# GPIOSheet.net
KiCad netlist of a schematic drawn in Altium Designer
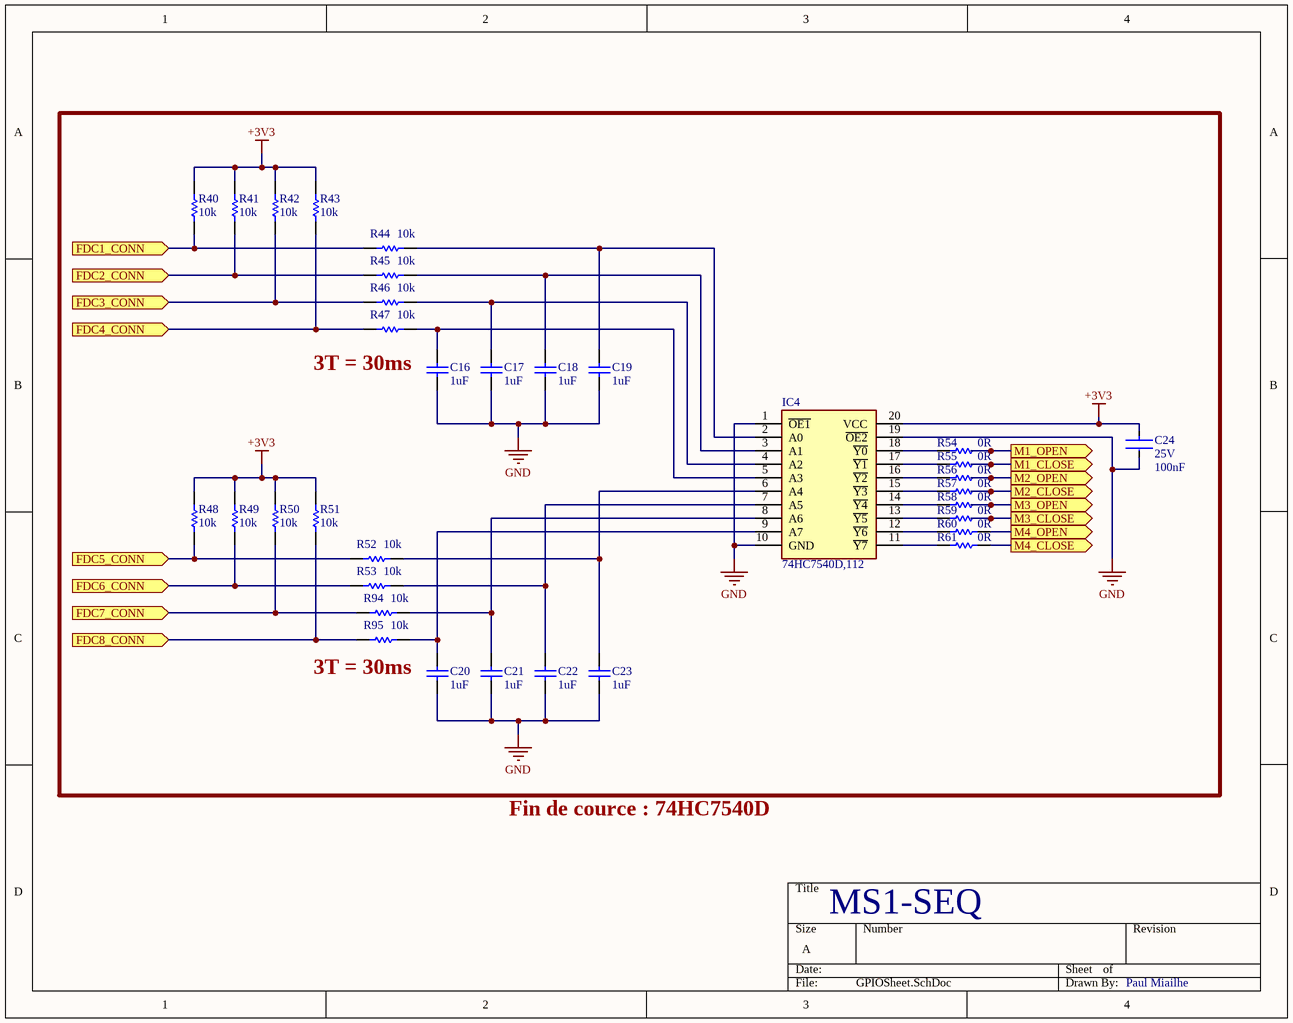
[diagram p0: GPIOSheet.SchDoc]

(export (version "E")
  (design (tool "Eeschema 10.0.6"))
  (components
    (comp (ref "C16")
      (value "GRM188R61E105KA12D")
      (footprint "CAPC1608X90X35LL10T15")
      (description "0603 1 uF 25 V ±10% Tolerance X5R SMT Multilayer Ceramic Capacitor")
      (fields
        (field (name "MANUFACTURER") "Murata")
        (field (name "CAPACITANCE") "1uF")
        (field (name "TOLERANCE") "10%")
      )
      (libsource (lib "Altium Content Vault") (part "CAP"))
    )
    (comp (ref "C17")
      (value "GRM188R61E105KA12D")
      (footprint "CAPC1608X90X35LL10T15")
      (description "0603 1 uF 25 V ±10% Tolerance X5R SMT Multilayer Ceramic Capacitor")
      (fields
        (field (name "MANUFACTURER") "Murata")
        (field (name "CAPACITANCE") "1uF")
        (field (name "TOLERANCE") "10%")
      )
      (libsource (lib "Altium Content Vault") (part "CAP"))
    )
    (comp (ref "C18")
      (value "GRM188R61E105KA12D")
      (footprint "CAPC1608X90X35LL10T15")
      (description "0603 1 uF 25 V ±10% Tolerance X5R SMT Multilayer Ceramic Capacitor")
      (fields
        (field (name "MANUFACTURER") "Murata")
        (field (name "CAPACITANCE") "1uF")
        (field (name "TOLERANCE") "10%")
      )
      (libsource (lib "Altium Content Vault") (part "CAP"))
    )
    (comp (ref "C19")
      (value "GRM188R61E105KA12D")
      (footprint "CAPC1608X90X35LL10T15")
      (description "0603 1 uF 25 V ±10% Tolerance X5R SMT Multilayer Ceramic Capacitor")
      (fields
        (field (name "MANUFACTURER") "Murata")
        (field (name "CAPACITANCE") "1uF")
        (field (name "TOLERANCE") "10%")
      )
      (libsource (lib "Altium Content Vault") (part "CAP"))
    )
    (comp (ref "C20")
      (value "GRM188R61E105KA12D")
      (footprint "CAPC1608X90X35LL10T15")
      (description "0603 1 uF 25 V ±10% Tolerance X5R SMT Multilayer Ceramic Capacitor")
      (fields
        (field (name "MANUFACTURER") "Murata")
        (field (name "CAPACITANCE") "1uF")
        (field (name "TOLERANCE") "10%")
      )
      (libsource (lib "Altium Content Vault") (part "CAP"))
    )
    (comp (ref "C21")
      (value "GRM188R61E105KA12D")
      (footprint "CAPC1608X90X35LL10T15")
      (description "0603 1 uF 25 V ±10% Tolerance X5R SMT Multilayer Ceramic Capacitor")
      (fields
        (field (name "MANUFACTURER") "Murata")
        (field (name "CAPACITANCE") "1uF")
        (field (name "TOLERANCE") "10%")
      )
      (libsource (lib "Altium Content Vault") (part "CAP"))
    )
    (comp (ref "C22")
      (value "GRM188R61E105KA12D")
      (footprint "CAPC1608X90X35LL10T15")
      (description "0603 1 uF 25 V ±10% Tolerance X5R SMT Multilayer Ceramic Capacitor")
      (fields
        (field (name "MANUFACTURER") "Murata")
        (field (name "CAPACITANCE") "1uF")
        (field (name "TOLERANCE") "10%")
      )
      (libsource (lib "Altium Content Vault") (part "CAP"))
    )
    (comp (ref "C23")
      (value "GRM188R61E105KA12D")
      (footprint "CAPC1608X90X35LL10T15")
      (description "0603 1 uF 25 V ±10% Tolerance X5R SMT Multilayer Ceramic Capacitor")
      (fields
        (field (name "MANUFACTURER") "Murata")
        (field (name "CAPACITANCE") "1uF")
        (field (name "TOLERANCE") "10%")
      )
      (libsource (lib "Altium Content Vault") (part "CAP"))
    )
    (comp (ref "C24")
      (value "CGA3E2X7R1E104K080AA")
      (footprint "FP-CGA3E-0_3-0_1-MFG")
      (description "Cap Ceramic 100nF 25V X7R 10% Pad SMD 0603 +125°C Automotive T/R")
      (fields
        (field (name "VOLTAGE RATING (DC)") "25V")
        (field (name "CAPACITANCE") "100nF")
        (field (name "TOLERANCE") "10%")
        (field (name "MANUFACTURER") "TDK")
      )
      (libsource (lib "Altium Content Vault") (part "b4654b650e69147ec39a6b967a45e02"))
    )
    (comp (ref "IC4")
      (value "74HC7540D,112")
      (footprint "SamacSys:SOIC127P1032X265-20N")
      (description "Integrated Circuit")
      (fields (field (name "MOUSER PART NUMBER") "771-HC7540D112"))
      (libsource (lib "*") (part "74HC7540D,112"))
    )
    (comp (ref "R40")
      (value "ERJ3EKF1002V")
      (footprint "RESC1609X55X30LL15T15")
      (description "Chip Resistor, 10 KOhm, +/- 1%, 0.1 W, -55 to 155 degC, 0603 (1608 Metric), RoHS, Tape and Reel")
      (fields
        (field (name "RESISTANCE") "10k")
        (field (name "TOLERANCE") "1%")
        (field (name "MANUFACTURER") "Panasonic")
      )
      (libsource (lib "Altium Content Vault") (part "RES-2"))
    )
    (comp (ref "R41")
      (value "ERJ3EKF1002V")
      (footprint "RESC1609X55X30LL15T15")
      (description "Chip Resistor, 10 KOhm, +/- 1%, 0.1 W, -55 to 155 degC, 0603 (1608 Metric), RoHS, Tape and Reel")
      (fields
        (field (name "RESISTANCE") "10k")
        (field (name "TOLERANCE") "1%")
        (field (name "MANUFACTURER") "Panasonic")
      )
      (libsource (lib "Altium Content Vault") (part "RES-2"))
    )
    (comp (ref "R42")
      (value "ERJ3EKF1002V")
      (footprint "RESC1609X55X30LL15T15")
      (description "Chip Resistor, 10 KOhm, +/- 1%, 0.1 W, -55 to 155 degC, 0603 (1608 Metric), RoHS, Tape and Reel")
      (fields
        (field (name "RESISTANCE") "10k")
        (field (name "TOLERANCE") "1%")
        (field (name "MANUFACTURER") "Panasonic")
      )
      (libsource (lib "Altium Content Vault") (part "RES-2"))
    )
    (comp (ref "R43")
      (value "ERJ3EKF1002V")
      (footprint "RESC1609X55X30LL15T15")
      (description "Chip Resistor, 10 KOhm, +/- 1%, 0.1 W, -55 to 155 degC, 0603 (1608 Metric), RoHS, Tape and Reel")
      (fields
        (field (name "RESISTANCE") "10k")
        (field (name "TOLERANCE") "1%")
        (field (name "MANUFACTURER") "Panasonic")
      )
      (libsource (lib "Altium Content Vault") (part "RES-2"))
    )
    (comp (ref "R44")
      (value "ERJ3EKF1002V")
      (footprint "RESC1609X55X30LL15T15")
      (description "Chip Resistor, 10 KOhm, +/- 1%, 0.1 W, -55 to 155 degC, 0603 (1608 Metric), RoHS, Tape and Reel")
      (fields
        (field (name "RESISTANCE") "10k")
        (field (name "TOLERANCE") "1%")
        (field (name "MANUFACTURER") "Panasonic")
      )
      (libsource (lib "Altium Content Vault") (part "RES-2"))
    )
    (comp (ref "R45")
      (value "ERJ3EKF1002V")
      (footprint "RESC1609X55X30LL15T15")
      (description "Chip Resistor, 10 KOhm, +/- 1%, 0.1 W, -55 to 155 degC, 0603 (1608 Metric), RoHS, Tape and Reel")
      (fields
        (field (name "RESISTANCE") "10k")
        (field (name "TOLERANCE") "1%")
        (field (name "MANUFACTURER") "Panasonic")
      )
      (libsource (lib "Altium Content Vault") (part "RES-2"))
    )
    (comp (ref "R46")
      (value "ERJ3EKF1002V")
      (footprint "RESC1609X55X30LL15T15")
      (description "Chip Resistor, 10 KOhm, +/- 1%, 0.1 W, -55 to 155 degC, 0603 (1608 Metric), RoHS, Tape and Reel")
      (fields
        (field (name "RESISTANCE") "10k")
        (field (name "TOLERANCE") "1%")
        (field (name "MANUFACTURER") "Panasonic")
      )
      (libsource (lib "Altium Content Vault") (part "RES-2"))
    )
    (comp (ref "R47")
      (value "ERJ3EKF1002V")
      (footprint "RESC1609X55X30LL15T15")
      (description "Chip Resistor, 10 KOhm, +/- 1%, 0.1 W, -55 to 155 degC, 0603 (1608 Metric), RoHS, Tape and Reel")
      (fields
        (field (name "RESISTANCE") "10k")
        (field (name "TOLERANCE") "1%")
        (field (name "MANUFACTURER") "Panasonic")
      )
      (libsource (lib "Altium Content Vault") (part "RES-2"))
    )
    (comp (ref "R48")
      (value "ERJ3EKF1002V")
      (footprint "RESC1609X55X30LL15T15")
      (description "Chip Resistor, 10 KOhm, +/- 1%, 0.1 W, -55 to 155 degC, 0603 (1608 Metric), RoHS, Tape and Reel")
      (fields
        (field (name "RESISTANCE") "10k")
        (field (name "TOLERANCE") "1%")
        (field (name "MANUFACTURER") "Panasonic")
      )
      (libsource (lib "Altium Content Vault") (part "RES-2"))
    )
    (comp (ref "R49")
      (value "ERJ3EKF1002V")
      (footprint "RESC1609X55X30LL15T15")
      (description "Chip Resistor, 10 KOhm, +/- 1%, 0.1 W, -55 to 155 degC, 0603 (1608 Metric), RoHS, Tape and Reel")
      (fields
        (field (name "RESISTANCE") "10k")
        (field (name "TOLERANCE") "1%")
        (field (name "MANUFACTURER") "Panasonic")
      )
      (libsource (lib "Altium Content Vault") (part "RES-2"))
    )
    (comp (ref "R50")
      (value "ERJ3EKF1002V")
      (footprint "RESC1609X55X30LL15T15")
      (description "Chip Resistor, 10 KOhm, +/- 1%, 0.1 W, -55 to 155 degC, 0603 (1608 Metric), RoHS, Tape and Reel")
      (fields
        (field (name "RESISTANCE") "10k")
        (field (name "TOLERANCE") "1%")
        (field (name "MANUFACTURER") "Panasonic")
      )
      (libsource (lib "Altium Content Vault") (part "RES-2"))
    )
    (comp (ref "R51")
      (value "ERJ3EKF1002V")
      (footprint "RESC1609X55X30LL15T15")
      (description "Chip Resistor, 10 KOhm, +/- 1%, 0.1 W, -55 to 155 degC, 0603 (1608 Metric), RoHS, Tape and Reel")
      (fields
        (field (name "RESISTANCE") "10k")
        (field (name "TOLERANCE") "1%")
        (field (name "MANUFACTURER") "Panasonic")
      )
      (libsource (lib "Altium Content Vault") (part "RES-2"))
    )
    (comp (ref "R52")
      (value "ERJ3EKF1002V")
      (footprint "RESC1609X55X30LL15T15")
      (description "Chip Resistor, 10 KOhm, +/- 1%, 0.1 W, -55 to 155 degC, 0603 (1608 Metric), RoHS, Tape and Reel")
      (fields
        (field (name "RESISTANCE") "10k")
        (field (name "TOLERANCE") "1%")
        (field (name "MANUFACTURER") "Panasonic")
      )
      (libsource (lib "Altium Content Vault") (part "RES-2"))
    )
    (comp (ref "R53")
      (value "ERJ3EKF1002V")
      (footprint "RESC1609X55X30LL15T15")
      (description "Chip Resistor, 10 KOhm, +/- 1%, 0.1 W, -55 to 155 degC, 0603 (1608 Metric), RoHS, Tape and Reel")
      (fields
        (field (name "RESISTANCE") "10k")
        (field (name "TOLERANCE") "1%")
        (field (name "MANUFACTURER") "Panasonic")
      )
      (libsource (lib "Altium Content Vault") (part "RES-2"))
    )
    (comp (ref "R54")
      (value "0R")
      (footprint "RESC1608X55X25ML10T15")
      (description "Chip Resistor, 0 Ohm, +/- 5%, 0.1 W, -55 to 155 degC, 0603 (1608 Metric), RoHS, Tape and Reel")
      (fields (field (name "TOLERANCE") "5%") (field (name "MANUFACTURER") "Yageo"))
      (libsource (lib "Altium Content Vault") (part "RES-2"))
    )
    (comp (ref "R55")
      (value "0R")
      (footprint "RESC1608X55X25ML10T15")
      (description "Chip Resistor, 0 Ohm, +/- 5%, 0.1 W, -55 to 155 degC, 0603 (1608 Metric), RoHS, Tape and Reel")
      (fields (field (name "TOLERANCE") "5%") (field (name "MANUFACTURER") "Yageo"))
      (libsource (lib "Altium Content Vault") (part "RES-2"))
    )
    (comp (ref "R56")
      (value "0R")
      (footprint "RESC1608X55X25ML10T15")
      (description "Chip Resistor, 0 Ohm, +/- 5%, 0.1 W, -55 to 155 degC, 0603 (1608 Metric), RoHS, Tape and Reel")
      (fields (field (name "TOLERANCE") "5%") (field (name "MANUFACTURER") "Yageo"))
      (libsource (lib "Altium Content Vault") (part "RES-2"))
    )
    (comp (ref "R57")
      (value "0R")
      (footprint "RESC1608X55X25ML10T15")
      (description "Chip Resistor, 0 Ohm, +/- 5%, 0.1 W, -55 to 155 degC, 0603 (1608 Metric), RoHS, Tape and Reel")
      (fields (field (name "TOLERANCE") "5%") (field (name "MANUFACTURER") "Yageo"))
      (libsource (lib "Altium Content Vault") (part "RES-2"))
    )
    (comp (ref "R58")
      (value "0R")
      (footprint "RESC1608X55X25ML10T15")
      (description "Chip Resistor, 0 Ohm, +/- 5%, 0.1 W, -55 to 155 degC, 0603 (1608 Metric), RoHS, Tape and Reel")
      (fields (field (name "TOLERANCE") "5%") (field (name "MANUFACTURER") "Yageo"))
      (libsource (lib "Altium Content Vault") (part "RES-2"))
    )
    (comp (ref "R59")
      (value "0R")
      (footprint "RESC1608X55X25ML10T15")
      (description "Chip Resistor, 0 Ohm, +/- 5%, 0.1 W, -55 to 155 degC, 0603 (1608 Metric), RoHS, Tape and Reel")
      (fields (field (name "TOLERANCE") "5%") (field (name "MANUFACTURER") "Yageo"))
      (libsource (lib "Altium Content Vault") (part "RES-2"))
    )
    (comp (ref "R60")
      (value "0R")
      (footprint "RESC1608X55X25ML10T15")
      (description "Chip Resistor, 0 Ohm, +/- 5%, 0.1 W, -55 to 155 degC, 0603 (1608 Metric), RoHS, Tape and Reel")
      (fields (field (name "TOLERANCE") "5%") (field (name "MANUFACTURER") "Yageo"))
      (libsource (lib "Altium Content Vault") (part "RES-2"))
    )
    (comp (ref "R61")
      (value "0R")
      (footprint "RESC1608X55X25ML10T15")
      (description "Chip Resistor, 0 Ohm, +/- 5%, 0.1 W, -55 to 155 degC, 0603 (1608 Metric), RoHS, Tape and Reel")
      (fields (field (name "TOLERANCE") "5%") (field (name "MANUFACTURER") "Yageo"))
      (libsource (lib "Altium Content Vault") (part "RES-2"))
    )
    (comp (ref "R94")
      (value "ERJ3EKF1002V")
      (footprint "RESC1609X55X30LL15T15")
      (description "Chip Resistor, 10 KOhm, +/- 1%, 0.1 W, -55 to 155 degC, 0603 (1608 Metric), RoHS, Tape and Reel")
      (fields
        (field (name "RESISTANCE") "10k")
        (field (name "TOLERANCE") "1%")
        (field (name "MANUFACTURER") "Panasonic")
      )
      (libsource (lib "Altium Content Vault") (part "RES-2"))
    )
    (comp (ref "R95")
      (value "ERJ3EKF1002V")
      (footprint "RESC1609X55X30LL15T15")
      (description "Chip Resistor, 10 KOhm, +/- 1%, 0.1 W, -55 to 155 degC, 0603 (1608 Metric), RoHS, Tape and Reel")
      (fields
        (field (name "RESISTANCE") "10k")
        (field (name "TOLERANCE") "1%")
        (field (name "MANUFACTURER") "Panasonic")
      )
      (libsource (lib "Altium Content Vault") (part "RES-2"))
    )
  )
  (nets
    (net (code "1") (name "+3V3") (class "Default")
      (node (ref "C24") (pin "1") (pinfunction "1_1") (pintype "passive"))
      (node (ref "IC4") (pin "20") (pinfunction "VCC_20") (pintype "passive"))
      (node (ref "R40") (pin "2") (pinfunction "2_2") (pintype "passive"))
      (node (ref "R41") (pin "2") (pinfunction "2_2") (pintype "passive"))
      (node (ref "R42") (pin "2") (pinfunction "2_2") (pintype "passive"))
      (node (ref "R43") (pin "2") (pinfunction "2_2") (pintype "passive"))
      (node (ref "R48") (pin "2") (pinfunction "2_2") (pintype "passive"))
      (node (ref "R49") (pin "2") (pinfunction "2_2") (pintype "passive"))
      (node (ref "R50") (pin "2") (pinfunction "2_2") (pintype "passive"))
      (node (ref "R51") (pin "2") (pinfunction "2_2") (pintype "passive"))
    )
    (net (code "2") (name "/FDC1_CONN") (class "Default")
      (node (ref "R40") (pin "1") (pinfunction "1_1") (pintype "passive"))
      (node (ref "R44") (pin "2") (pinfunction "2_2") (pintype "passive"))
    )
    (net (code "3") (name "/FDC2_CONN") (class "Default")
      (node (ref "R41") (pin "1") (pinfunction "1_1") (pintype "passive"))
      (node (ref "R45") (pin "2") (pinfunction "2_2") (pintype "passive"))
    )
    (net (code "4") (name "/FDC3_CONN") (class "Default")
      (node (ref "R42") (pin "1") (pinfunction "1_1") (pintype "passive"))
      (node (ref "R46") (pin "2") (pinfunction "2_2") (pintype "passive"))
    )
    (net (code "5") (name "/FDC4_CONN") (class "Default")
      (node (ref "R43") (pin "1") (pinfunction "1_1") (pintype "passive"))
      (node (ref "R47") (pin "2") (pinfunction "2_2") (pintype "passive"))
    )
    (net (code "6") (name "/FDC5_CONN") (class "Default")
      (node (ref "R48") (pin "1") (pinfunction "1_1") (pintype "passive"))
      (node (ref "R52") (pin "2") (pinfunction "2_2") (pintype "passive"))
    )
    (net (code "7") (name "/FDC6_CONN") (class "Default")
      (node (ref "R49") (pin "1") (pinfunction "1_1") (pintype "passive"))
      (node (ref "R53") (pin "2") (pinfunction "2_2") (pintype "passive"))
    )
    (net (code "8") (name "/FDC7_CONN") (class "Default")
      (node (ref "R50") (pin "1") (pinfunction "1_1") (pintype "passive"))
      (node (ref "R94") (pin "2") (pinfunction "2_2") (pintype "passive"))
    )
    (net (code "9") (name "/FDC8_CONN") (class "Default")
      (node (ref "R51") (pin "1") (pinfunction "1_1") (pintype "passive"))
      (node (ref "R95") (pin "2") (pinfunction "2_2") (pintype "passive"))
    )
    (net (code "10") (name "/M1_CLOSE") (class "Default")
      (node (ref "R55") (pin "2") (pinfunction "2_2") (pintype "passive"))
    )
    (net (code "11") (name "/M1_OPEN") (class "Default")
      (node (ref "R54") (pin "2") (pinfunction "2_2") (pintype "passive"))
    )
    (net (code "12") (name "/M2_CLOSE") (class "Default")
      (node (ref "R57") (pin "2") (pinfunction "2_2") (pintype "passive"))
    )
    (net (code "13") (name "/M2_OPEN") (class "Default")
      (node (ref "R56") (pin "2") (pinfunction "2_2") (pintype "passive"))
    )
    (net (code "14") (name "/M3_CLOSE") (class "Default")
      (node (ref "R59") (pin "2") (pinfunction "2_2") (pintype "passive"))
    )
    (net (code "15") (name "/M3_OPEN") (class "Default")
      (node (ref "R58") (pin "2") (pinfunction "2_2") (pintype "passive"))
    )
    (net (code "16") (name "/M4_CLOSE") (class "Default")
      (node (ref "R61") (pin "2") (pinfunction "2_2") (pintype "passive"))
    )
    (net (code "17") (name "/M4_OPEN") (class "Default")
      (node (ref "R60") (pin "2") (pinfunction "2_2") (pintype "passive"))
    )
    (net (code "18") (name "GND") (class "Default")
      (node (ref "C16") (pin "1") (pinfunction "1_1") (pintype "passive"))
      (node (ref "C17") (pin "1") (pinfunction "1_1") (pintype "passive"))
      (node (ref "C18") (pin "1") (pinfunction "1_1") (pintype "passive"))
      (node (ref "C19") (pin "1") (pinfunction "1_1") (pintype "passive"))
      (node (ref "C20") (pin "1") (pinfunction "1_1") (pintype "passive"))
      (node (ref "C21") (pin "1") (pinfunction "1_1") (pintype "passive"))
      (node (ref "C22") (pin "1") (pinfunction "1_1") (pintype "passive"))
      (node (ref "C23") (pin "1") (pinfunction "1_1") (pintype "passive"))
      (node (ref "C24") (pin "2") (pinfunction "2_2") (pintype "passive"))
      (node (ref "IC4") (pin "1") (pinfunction "~{OE1}_1") (pintype "passive"))
      (node (ref "IC4") (pin "10") (pinfunction "GND_10") (pintype "passive"))
      (node (ref "IC4") (pin "19") (pinfunction "~{OE2}_19") (pintype "passive"))
    )
    (net (code "19") (name "Net-(IC4-A0)") (class "Default")
      (node (ref "C19") (pin "2") (pinfunction "2_2") (pintype "passive"))
      (node (ref "IC4") (pin "2") (pinfunction "A0_2") (pintype "passive"))
      (node (ref "R44") (pin "1") (pinfunction "1_1") (pintype "passive"))
    )
    (net (code "20") (name "Net-(IC4-A1)") (class "Default")
      (node (ref "C18") (pin "2") (pinfunction "2_2") (pintype "passive"))
      (node (ref "IC4") (pin "3") (pinfunction "A1_3") (pintype "passive"))
      (node (ref "R45") (pin "1") (pinfunction "1_1") (pintype "passive"))
    )
    (net (code "21") (name "Net-(IC4-A2)") (class "Default")
      (node (ref "C17") (pin "2") (pinfunction "2_2") (pintype "passive"))
      (node (ref "IC4") (pin "4") (pinfunction "A2_4") (pintype "passive"))
      (node (ref "R46") (pin "1") (pinfunction "1_1") (pintype "passive"))
    )
    (net (code "22") (name "Net-(IC4-A3)") (class "Default")
      (node (ref "C16") (pin "2") (pinfunction "2_2") (pintype "passive"))
      (node (ref "IC4") (pin "5") (pinfunction "A3_5") (pintype "passive"))
      (node (ref "R47") (pin "1") (pinfunction "1_1") (pintype "passive"))
    )
    (net (code "23") (name "Net-(IC4-A4)") (class "Default")
      (node (ref "C23") (pin "2") (pinfunction "2_2") (pintype "passive"))
      (node (ref "IC4") (pin "6") (pinfunction "A4_6") (pintype "passive"))
      (node (ref "R52") (pin "1") (pinfunction "1_1") (pintype "passive"))
    )
    (net (code "24") (name "Net-(IC4-A5)") (class "Default")
      (node (ref "C22") (pin "2") (pinfunction "2_2") (pintype "passive"))
      (node (ref "IC4") (pin "7") (pinfunction "A5_7") (pintype "passive"))
      (node (ref "R53") (pin "1") (pinfunction "1_1") (pintype "passive"))
    )
    (net (code "25") (name "Net-(IC4-A6)") (class "Default")
      (node (ref "C21") (pin "2") (pinfunction "2_2") (pintype "passive"))
      (node (ref "IC4") (pin "8") (pinfunction "A6_8") (pintype "passive"))
      (node (ref "R94") (pin "1") (pinfunction "1_1") (pintype "passive"))
    )
    (net (code "26") (name "Net-(IC4-A7)") (class "Default")
      (node (ref "C20") (pin "2") (pinfunction "2_2") (pintype "passive"))
      (node (ref "IC4") (pin "9") (pinfunction "A7_9") (pintype "passive"))
      (node (ref "R95") (pin "1") (pinfunction "1_1") (pintype "passive"))
    )
    (net (code "27") (name "Net-(IC4-~{Y0})") (class "Default")
      (node (ref "IC4") (pin "18") (pinfunction "~{Y0}_18") (pintype "passive"))
      (node (ref "R54") (pin "1") (pinfunction "1_1") (pintype "passive"))
    )
    (net (code "28") (name "Net-(IC4-~{Y1})") (class "Default")
      (node (ref "IC4") (pin "17") (pinfunction "~{Y1}_17") (pintype "passive"))
      (node (ref "R55") (pin "1") (pinfunction "1_1") (pintype "passive"))
    )
    (net (code "29") (name "Net-(IC4-~{Y2})") (class "Default")
      (node (ref "IC4") (pin "16") (pinfunction "~{Y2}_16") (pintype "passive"))
      (node (ref "R56") (pin "1") (pinfunction "1_1") (pintype "passive"))
    )
    (net (code "30") (name "Net-(IC4-~{Y3})") (class "Default")
      (node (ref "IC4") (pin "15") (pinfunction "~{Y3}_15") (pintype "passive"))
      (node (ref "R57") (pin "1") (pinfunction "1_1") (pintype "passive"))
    )
    (net (code "31") (name "Net-(IC4-~{Y4})") (class "Default")
      (node (ref "IC4") (pin "14") (pinfunction "~{Y4}_14") (pintype "passive"))
      (node (ref "R58") (pin "1") (pinfunction "1_1") (pintype "passive"))
    )
    (net (code "32") (name "Net-(IC4-~{Y5})") (class "Default")
      (node (ref "IC4") (pin "13") (pinfunction "~{Y5}_13") (pintype "passive"))
      (node (ref "R59") (pin "1") (pinfunction "1_1") (pintype "passive"))
    )
    (net (code "33") (name "Net-(IC4-~{Y6})") (class "Default")
      (node (ref "IC4") (pin "12") (pinfunction "~{Y6}_12") (pintype "passive"))
      (node (ref "R60") (pin "1") (pinfunction "1_1") (pintype "passive"))
    )
    (net (code "34") (name "Net-(IC4-~{Y7})") (class "Default")
      (node (ref "IC4") (pin "11") (pinfunction "~{Y7}_11") (pintype "passive"))
      (node (ref "R61") (pin "1") (pinfunction "1_1") (pintype "passive"))
    )
  )
)
